# power.net
KiCad netlist of a schematic drawn in Altium Designer
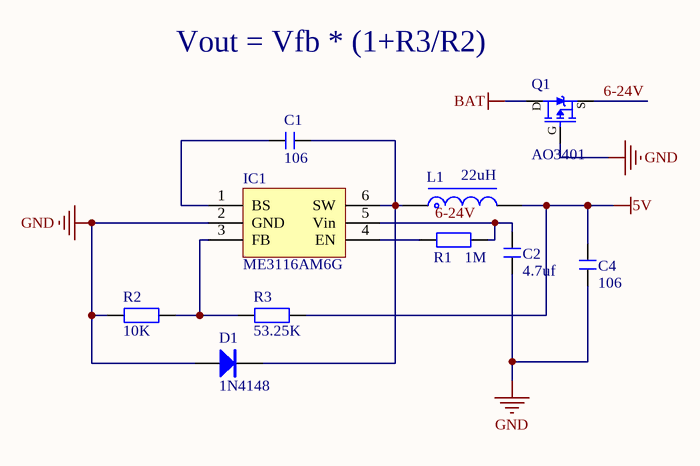
[diagram p0: power.SchDoc]

(export (version "E")
  (design (tool "Eeschema 10.0.6"))
  (components
    (comp (ref "C1")
      (value "106")
      (footprint "C 0603_L")
      (description "无极性贴片电容")
      (fields (field (name "版权归属") "源创客"))
      (libsource (lib "3.1   - 电阻-电容-电感") (part "C"))
    )
    (comp (ref "C2")
      (value "4.7uf")
      (footprint "C 0603_L")
      (description "无极性贴片电容")
      (fields (field (name "版权归属") "源创客"))
      (libsource (lib "3.1   - 电阻-电容-电感") (part "C"))
    )
    (comp (ref "C4")
      (value "106")
      (footprint "C 0603_L")
      (description "无极性贴片电容")
      (fields (field (name "版权归属") "源创客"))
      (libsource (lib "3.1   - 电阻-电容-电感") (part "C"))
    )
    (comp (ref "D1")
      (value "1N4148")
      (footprint "SOD-323")
      (description "高速开关二极管")
      (fields (field (name "版权归属") "源创客"))
      (libsource (lib "8.1   - 二极管-整流桥") (part "1N4148"))
    )
    (comp (ref "IC1")
      (value "ME3116AM6G")
      (footprint "SOT23-6N")
      (description "可调升压芯片")
      (fields (field (name "版权归属") "源创客"))
      (libsource (lib "1.3   - 电源类芯片") (part "SX1308"))
    )
    (comp (ref "L1")
      (value "22uH")
      (footprint "NR2520")
      (description "NR磁胶电感")
      (fields (field (name "版权归属") "源创客"))
      (libsource (lib "3.1   - 电阻-电容-电感") (part "L-NR"))
    )
    (comp (ref "Q1")
      (value "AO3401")
      (footprint "SOT23-3L")
      (description "P沟道 30V/4.2A")
      (fields (field (name "版权归属") "源创客"))
      (libsource (lib "6.1   - 场效应管-可控硅") (part "AO3401"))
    )
    (comp (ref "R1")
      (value "1M")
      (footprint "R 0603_L")
      (description "贴片电阻")
      (fields (field (name "版权归属") "源创客"))
      (libsource (lib "3.1   - 电阻-电容-电感") (part "R"))
    )
    (comp (ref "R2")
      (value "10K")
      (footprint "R 0603_L")
      (description "贴片电阻")
      (fields (field (name "版权归属") "源创客"))
      (libsource (lib "3.1   - 电阻-电容-电感") (part "R"))
    )
    (comp (ref "R3")
      (value "53.25K")
      (footprint "R 0603_L")
      (description "贴片电阻")
      (fields (field (name "版权归属") "源创客"))
      (libsource (lib "3.1   - 电阻-电容-电感") (part "R"))
    )
  )
  (nets
    (net (code "1") (name "/6-24V") (class "Default")
      (node (ref "C2") (pin "2") (pinfunction "2_2") (pintype "passive"))
      (node (ref "IC1") (pin "5") (pinfunction "Vin_5") (pintype "passive"))
      (node (ref "Q1") (pin "2") (pinfunction "S_2") (pintype "passive"))
      (node (ref "R1") (pin "2") (pinfunction "2_2") (pintype "passive"))
    )
    (net (code "2") (name "5V") (class "Default")
      (node (ref "C4") (pin "2") (pinfunction "2_2") (pintype "passive"))
      (node (ref "L1") (pin "2") (pinfunction "2_2") (pintype "passive"))
      (node (ref "R3") (pin "2") (pinfunction "2_2") (pintype "passive"))
    )
    (net (code "3") (name "BAT") (class "Default")
      (node (ref "Q1") (pin "3") (pinfunction "D_3") (pintype "passive"))
    )
    (net (code "4") (name "GND") (class "Default")
      (node (ref "C2") (pin "1") (pinfunction "1_1") (pintype "passive"))
      (node (ref "C4") (pin "1") (pinfunction "1_1") (pintype "passive"))
      (node (ref "D1") (pin "1") (pinfunction "A_1") (pintype "passive"))
      (node (ref "IC1") (pin "2") (pinfunction "GND_2") (pintype "passive"))
      (node (ref "Q1") (pin "1") (pinfunction "G_1") (pintype "passive"))
      (node (ref "R2") (pin "1") (pinfunction "1_1") (pintype "passive"))
    )
    (net (code "5") (name "Net-(D1-K)") (class "Default")
      (node (ref "C1") (pin "2") (pinfunction "2_2") (pintype "passive"))
      (node (ref "D1") (pin "2") (pinfunction "K_2") (pintype "passive"))
      (node (ref "IC1") (pin "6") (pinfunction "SW_6") (pintype "passive"))
      (node (ref "L1") (pin "1") (pinfunction "1_1") (pintype "passive"))
    )
    (net (code "6") (name "Net-(IC1-BS)") (class "Default")
      (node (ref "C1") (pin "1") (pinfunction "1_1") (pintype "passive"))
      (node (ref "IC1") (pin "1") (pinfunction "BS_1") (pintype "passive"))
    )
    (net (code "7") (name "Net-(IC1-EN)") (class "Default")
      (node (ref "IC1") (pin "4") (pinfunction "EN_4") (pintype "passive"))
      (node (ref "R1") (pin "1") (pinfunction "1_1") (pintype "passive"))
    )
    (net (code "8") (name "Net-(IC1-FB)") (class "Default")
      (node (ref "IC1") (pin "3") (pinfunction "FB_3") (pintype "passive"))
      (node (ref "R2") (pin "2") (pinfunction "2_2") (pintype "passive"))
      (node (ref "R3") (pin "1") (pinfunction "1_1") (pintype "passive"))
    )
  )
)
